# Sensor_Board_0x09_Prototyping_v1.net
KiCad netlist of a schematic drawn in EAGLE
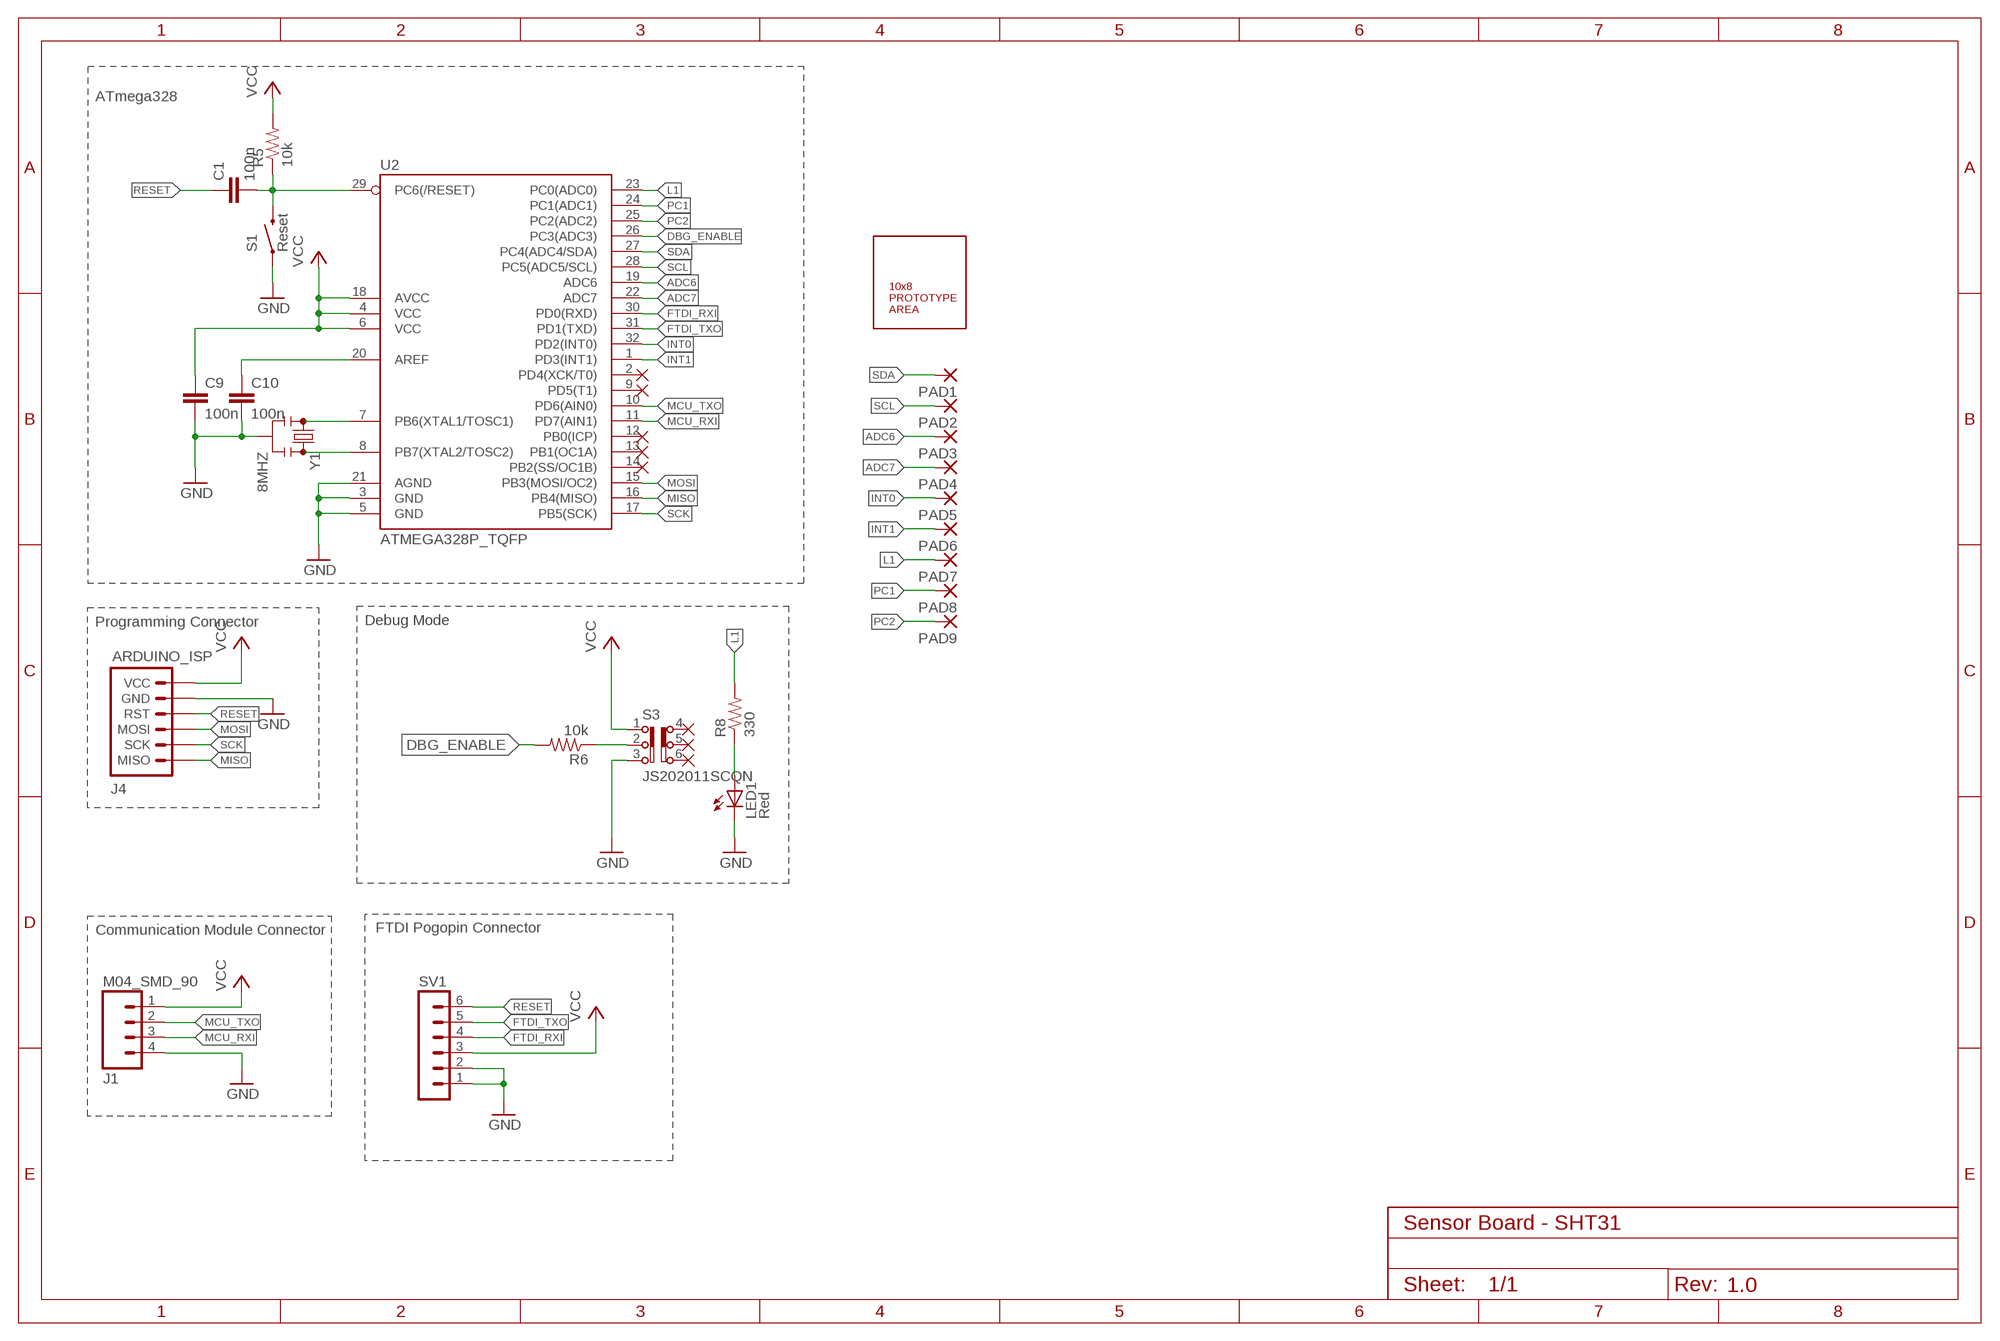
[diagram p0: schematic, sheet 1]

(export (version "E")
  (design (tool "Eeschema 10.0.6"))
  (components
    (comp (ref "C1")
      (value "100n")
      (footprint "eagle-import:C0805")
      (libsource (lib "eagle-import") (part "C"))
    )
    (comp (ref "C9")
      (value "100n")
      (footprint "eagle-import:C0805")
      (libsource (lib "eagle-import") (part "C"))
    )
    (comp (ref "C10")
      (value "100n")
      (footprint "eagle-import:C0805")
      (libsource (lib "eagle-import") (part "C"))
    )
    (comp (ref "J1")
      (value "M04_SMD_90")
      (footprint "eagle-import:M04_SMD_90")
      (libsource (lib "eagle-import") (part "M04_SMD_90"))
    )
    (comp (ref "J4")
      (value "ARDUINO_ISP")
      (footprint "eagle-import:M-2X3")
      (libsource (lib "eagle-import") (part "ARDUINO_ISP"))
    )
    (comp (ref "LED1")
      (value "Red")
      (footprint "eagle-import:SML0805")
      (libsource (lib "eagle-import") (part "LEDSML0805"))
    )
    (comp (ref "PAD1")
      (value "1,6/0,9")
      (footprint "eagle-import:1,6_0,9")
      (libsource (lib "eagle-import") (part "1,6/0,9"))
    )
    (comp (ref "PAD2")
      (value "1,6/0,9")
      (footprint "eagle-import:1,6_0,9")
      (libsource (lib "eagle-import") (part "1,6/0,9"))
    )
    (comp (ref "PAD3")
      (value "1,6/0,9")
      (footprint "eagle-import:1,6_0,9")
      (libsource (lib "eagle-import") (part "1,6/0,9"))
    )
    (comp (ref "PAD4")
      (value "1,6/0,9")
      (footprint "eagle-import:1,6_0,9")
      (libsource (lib "eagle-import") (part "1,6/0,9"))
    )
    (comp (ref "PAD5")
      (value "1,6/0,9")
      (footprint "eagle-import:1,6_0,9")
      (libsource (lib "eagle-import") (part "1,6/0,9"))
    )
    (comp (ref "PAD6")
      (value "1,6/0,9")
      (footprint "eagle-import:1,6_0,9")
      (libsource (lib "eagle-import") (part "1,6/0,9"))
    )
    (comp (ref "PAD7")
      (value "1,6/0,9")
      (footprint "eagle-import:1,6_0,9")
      (libsource (lib "eagle-import") (part "1,6/0,9"))
    )
    (comp (ref "PAD8")
      (value "1,6/0,9")
      (footprint "eagle-import:1,6_0,9")
      (libsource (lib "eagle-import") (part "1,6/0,9"))
    )
    (comp (ref "PAD9")
      (value "1,6/0,9")
      (footprint "eagle-import:1,6_0,9")
      (libsource (lib "eagle-import") (part "1,6/0,9"))
    )
    (comp (ref "R5")
      (value "10k")
      (footprint "eagle-import:0805")
      (libsource (lib "eagle-import") (part "RESISTOR0805-RES"))
    )
    (comp (ref "R6")
      (value "10k")
      (footprint "eagle-import:0805")
      (libsource (lib "eagle-import") (part "RESISTOR0805-RES"))
    )
    (comp (ref "R8")
      (value "330")
      (footprint "eagle-import:0805")
      (libsource (lib "eagle-import") (part "RESISTOR0805-RES"))
    )
    (comp (ref "S1")
      (value "Reset")
      (footprint "eagle-import:M-PUSHBUTTON-SMD")
      (libsource (lib "eagle-import") (part "PUSHBUTTON"))
    )
    (comp (ref "S3")
      (value "JS202011SCQN")
      (footprint "eagle-import:JS202011SCQN")
      (libsource (lib "eagle-import") (part "JS202011SCQN"))
    )
    (comp (ref "SV1")
      (value "MA06-1")
      (footprint "eagle-import:MA06-1")
      (libsource (lib "eagle-import") (part "MA06-1"))
    )
    (comp (ref "U$1")
      (value "10X8_PROTOTYPE_AREA")
      (footprint "eagle-import:10X8_PROTOTYPE_AREA")
      (libsource (lib "eagle-import") (part "10X8_PROTOTYPE_AREA"))
    )
    (comp (ref "U2")
      (value "ATMEGA328P_TQFP")
      (footprint "eagle-import:TQFP32-08")
      (libsource (lib "eagle-import") (part "ATMEGA328P_TQFP"))
    )
    (comp (ref "Y1")
      (value "8MHZ")
      (footprint "eagle-import:RESONATOR-SMD")
      (libsource (lib "eagle-import") (part "RESONATOR8MHZ"))
    )
  )
  (nets
    (net (code "1") (name "ADC6") (class "Default")
      (node (ref "PAD3") (pin "1") (pinfunction "P_1") (pintype "passive"))
      (node (ref "U2") (pin "19") (pinfunction "ADC6_19") (pintype "bidirectional"))
    )
    (net (code "2") (name "ADC7") (class "Default")
      (node (ref "PAD4") (pin "1") (pinfunction "P_1") (pintype "passive"))
      (node (ref "U2") (pin "22") (pinfunction "ADC7_22") (pintype "bidirectional"))
    )
    (net (code "3") (name "DBG_ENABLE") (class "Default")
      (node (ref "R6") (pin "2") (pinfunction "2_2") (pintype "passive"))
      (node (ref "U2") (pin "26") (pinfunction "PC3(ADC3)_26") (pintype "bidirectional"))
    )
    (net (code "4") (name "FTDI_RXI") (class "Default")
      (node (ref "SV1") (pin "4") (pinfunction "4_4") (pintype "passive"))
      (node (ref "U2") (pin "30") (pinfunction "PD0(RXD)_30") (pintype "bidirectional"))
    )
    (net (code "5") (name "FTDI_TXO") (class "Default")
      (node (ref "SV1") (pin "5") (pinfunction "5_5") (pintype "passive"))
      (node (ref "U2") (pin "31") (pinfunction "PD1(TXD)_31") (pintype "bidirectional"))
    )
    (net (code "6") (name "GND") (class "Default")
      (node (ref "C10") (pin "2") (pinfunction "2_2") (pintype "passive"))
      (node (ref "C9") (pin "2") (pinfunction "2_2") (pintype "passive"))
      (node (ref "J1") (pin "4") (pinfunction "4_4") (pintype "passive"))
      (node (ref "J4") (pin "P$5") (pinfunction "GND_P$5") (pintype "passive"))
      (node (ref "LED1") (pin "C") (pinfunction "C_C") (pintype "passive"))
      (node (ref "S1") (pin "1") (pinfunction "LEFT_1") (pintype "passive"))
      (node (ref "S1") (pin "2") (pinfunction "LEFT_2") (pintype "passive"))
      (node (ref "S3") (pin "3") (pinfunction "3_3") (pintype "passive"))
      (node (ref "SV1") (pin "1") (pinfunction "1_1") (pintype "passive"))
      (node (ref "SV1") (pin "2") (pinfunction "2_2") (pintype "passive"))
      (node (ref "U2") (pin "21") (pinfunction "AGND_21") (pintype "bidirectional"))
      (node (ref "U2") (pin "3") (pinfunction "GND_3") (pintype "bidirectional"))
      (node (ref "U2") (pin "5") (pinfunction "GND_5") (pintype "bidirectional"))
      (node (ref "Y1") (pin "2") (pinfunction "2_2") (pintype "passive"))
    )
    (net (code "7") (name "INT0") (class "Default")
      (node (ref "PAD5") (pin "1") (pinfunction "P_1") (pintype "passive"))
      (node (ref "U2") (pin "32") (pinfunction "PD2(INT0)_32") (pintype "bidirectional"))
    )
    (net (code "8") (name "INT1") (class "Default")
      (node (ref "PAD6") (pin "1") (pinfunction "P_1") (pintype "passive"))
      (node (ref "U2") (pin "1") (pinfunction "PD3(INT1)_1") (pintype "bidirectional"))
    )
    (net (code "9") (name "L1") (class "Default")
      (node (ref "PAD7") (pin "1") (pinfunction "P_1") (pintype "passive"))
      (node (ref "R8") (pin "2") (pinfunction "2_2") (pintype "passive"))
      (node (ref "U2") (pin "23") (pinfunction "PC0(ADC0)_23") (pintype "bidirectional"))
    )
    (net (code "10") (name "MCU_RXI") (class "Default")
      (node (ref "J1") (pin "3") (pinfunction "3_3") (pintype "passive"))
      (node (ref "U2") (pin "11") (pinfunction "PD7(AIN1)_11") (pintype "bidirectional"))
    )
    (net (code "11") (name "MCU_TXO") (class "Default")
      (node (ref "J1") (pin "2") (pinfunction "2_2") (pintype "passive"))
      (node (ref "U2") (pin "10") (pinfunction "PD6(AIN0)_10") (pintype "bidirectional"))
    )
    (net (code "12") (name "MISO") (class "Default")
      (node (ref "J4") (pin "P$1") (pinfunction "MISO_P$1") (pintype "passive"))
      (node (ref "U2") (pin "16") (pinfunction "PB4(MISO)_16") (pintype "bidirectional"))
    )
    (net (code "13") (name "MOSI") (class "Default")
      (node (ref "J4") (pin "P$3") (pinfunction "MOSI_P$3") (pintype "passive"))
      (node (ref "U2") (pin "15") (pinfunction "PB3(MOSI/OC2)_15") (pintype "bidirectional"))
    )
    (net (code "14") (name "Net-(LED1-PadA)") (class "Default")
      (node (ref "LED1") (pin "A") (pinfunction "A_A") (pintype "passive"))
      (node (ref "R8") (pin "1") (pinfunction "1_1") (pintype "passive"))
    )
    (net (code "15") (name "Net-(R6-Pad1)") (class "Default")
      (node (ref "R6") (pin "1") (pinfunction "1_1") (pintype "passive"))
      (node (ref "S3") (pin "2") (pinfunction "2_2") (pintype "passive"))
    )
    (net (code "16") (name "Net-(U2-AREF)") (class "Default")
      (node (ref "C10") (pin "1") (pinfunction "1_1") (pintype "passive"))
      (node (ref "U2") (pin "20") (pinfunction "AREF_20") (pintype "bidirectional"))
    )
    (net (code "17") (name "Net-(U2-PB6(XTAL1{slash}TOSC1))") (class "Default")
      (node (ref "U2") (pin "7") (pinfunction "PB6(XTAL1/TOSC1)_7") (pintype "bidirectional"))
      (node (ref "Y1") (pin "1") (pinfunction "1_1") (pintype "passive"))
    )
    (net (code "18") (name "Net-(U2-PB7(XTAL2{slash}TOSC2))") (class "Default")
      (node (ref "U2") (pin "8") (pinfunction "PB7(XTAL2/TOSC2)_8") (pintype "bidirectional"))
      (node (ref "Y1") (pin "3") (pinfunction "3_3") (pintype "passive"))
    )
    (net (code "19") (name "Net-(U2-PC6({slash}RESET))") (class "Default")
      (node (ref "C1") (pin "2") (pinfunction "2_2") (pintype "passive"))
      (node (ref "R5") (pin "1") (pinfunction "1_1") (pintype "passive"))
      (node (ref "S1") (pin "3") (pinfunction "RIGHT_3") (pintype "passive"))
      (node (ref "S1") (pin "4") (pinfunction "RIGHT_4") (pintype "passive"))
      (node (ref "U2") (pin "29") (pinfunction "PC6(/RESET)_29") (pintype "bidirectional"))
    )
    (net (code "20") (name "PC1") (class "Default")
      (node (ref "PAD8") (pin "1") (pinfunction "P_1") (pintype "passive"))
      (node (ref "U2") (pin "24") (pinfunction "PC1(ADC1)_24") (pintype "bidirectional"))
    )
    (net (code "21") (name "PC2") (class "Default")
      (node (ref "PAD9") (pin "1") (pinfunction "P_1") (pintype "passive"))
      (node (ref "U2") (pin "25") (pinfunction "PC2(ADC2)_25") (pintype "bidirectional"))
    )
    (net (code "22") (name "RESET") (class "Default")
      (node (ref "C1") (pin "1") (pinfunction "1_1") (pintype "passive"))
      (node (ref "J4") (pin "P$4") (pinfunction "RST_P$4") (pintype "passive"))
      (node (ref "SV1") (pin "6") (pinfunction "6_6") (pintype "passive"))
    )
    (net (code "23") (name "SCK") (class "Default")
      (node (ref "J4") (pin "P$2") (pinfunction "SCK_P$2") (pintype "passive"))
      (node (ref "U2") (pin "17") (pinfunction "PB5(SCK)_17") (pintype "bidirectional"))
    )
    (net (code "24") (name "SCL") (class "Default")
      (node (ref "PAD2") (pin "1") (pinfunction "P_1") (pintype "passive"))
      (node (ref "U2") (pin "28") (pinfunction "PC5(ADC5/SCL)_28") (pintype "bidirectional"))
    )
    (net (code "25") (name "SDA") (class "Default")
      (node (ref "PAD1") (pin "1") (pinfunction "P_1") (pintype "passive"))
      (node (ref "U2") (pin "27") (pinfunction "PC4(ADC4/SDA)_27") (pintype "bidirectional"))
    )
    (net (code "26") (name "VCC") (class "Default")
      (node (ref "C9") (pin "1") (pinfunction "1_1") (pintype "passive"))
      (node (ref "J1") (pin "1") (pinfunction "1_1") (pintype "passive"))
      (node (ref "J4") (pin "P$6") (pinfunction "VCC_P$6") (pintype "passive"))
      (node (ref "R5") (pin "2") (pinfunction "2_2") (pintype "passive"))
      (node (ref "S3") (pin "1") (pinfunction "1_1") (pintype "passive"))
      (node (ref "SV1") (pin "3") (pinfunction "3_3") (pintype "passive"))
      (node (ref "U2") (pin "18") (pinfunction "AVCC_18") (pintype "bidirectional"))
      (node (ref "U2") (pin "4") (pinfunction "VCC_4") (pintype "bidirectional"))
      (node (ref "U2") (pin "6") (pinfunction "VCC_6") (pintype "bidirectional"))
    )
    (net (code "27") (name "unconnected-(S3-Pad4)") (class "Default")
      (node (ref "S3") (pin "4") (pinfunction "4_4") (pintype "passive"))
    )
    (net (code "28") (name "unconnected-(S3-Pad5)") (class "Default")
      (node (ref "S3") (pin "5") (pinfunction "5_5") (pintype "passive"))
    )
    (net (code "29") (name "unconnected-(S3-Pad6)") (class "Default")
      (node (ref "S3") (pin "6") (pinfunction "6_6") (pintype "passive"))
    )
    (net (code "30") (name "unconnected-(U2-PB0(ICP)-Pad12)") (class "Default")
      (node (ref "U2") (pin "12") (pinfunction "PB0(ICP)_12") (pintype "bidirectional"))
    )
    (net (code "31") (name "unconnected-(U2-PB1(OC1A)-Pad13)") (class "Default")
      (node (ref "U2") (pin "13") (pinfunction "PB1(OC1A)_13") (pintype "bidirectional"))
    )
    (net (code "32") (name "unconnected-(U2-PB2(SS{slash}OC1B)-Pad14)") (class "Default")
      (node (ref "U2") (pin "14") (pinfunction "PB2(SS/OC1B)_14") (pintype "bidirectional"))
    )
    (net (code "33") (name "unconnected-(U2-PD4(XCK{slash}T0)-Pad2)") (class "Default")
      (node (ref "U2") (pin "2") (pinfunction "PD4(XCK/T0)_2") (pintype "bidirectional"))
    )
    (net (code "34") (name "unconnected-(U2-PD5(T1)-Pad9)") (class "Default")
      (node (ref "U2") (pin "9") (pinfunction "PD5(T1)_9") (pintype "bidirectional"))
    )
  )
)
